# Amplifiers.net
KiCad netlist of a schematic drawn in Altium Designer
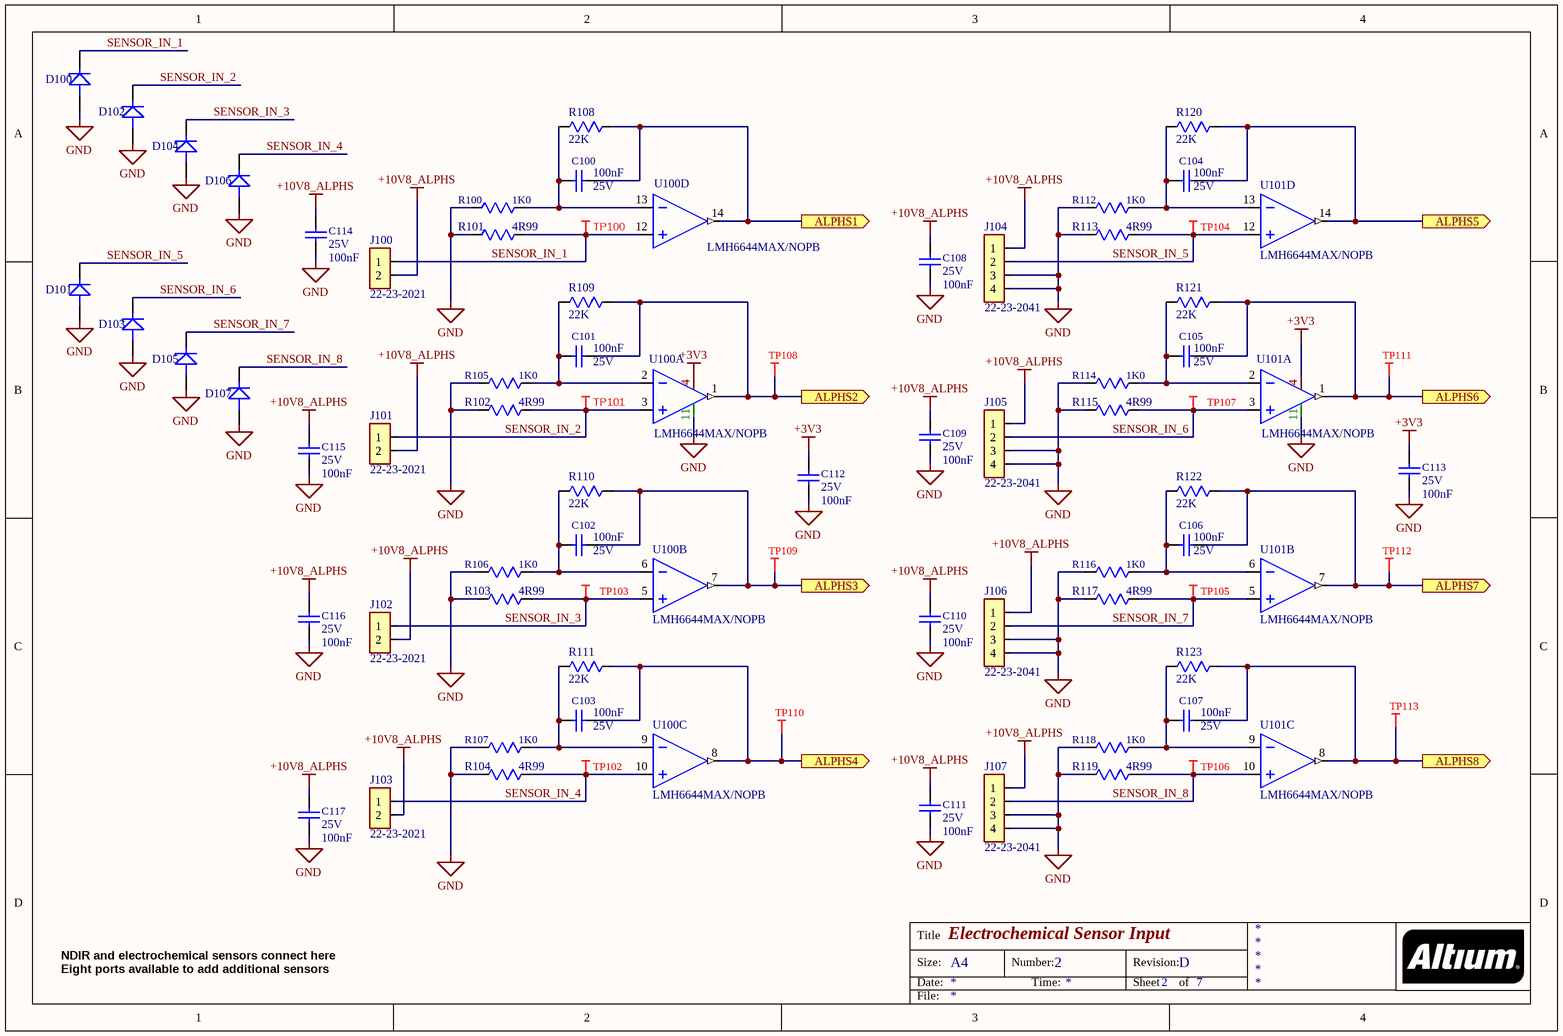
[diagram p0: Amplifiers.SchDoc]

(export (version "E")
  (design (tool "Eeschema 10.0.6"))
  (components
    (comp (ref "C100")
      (value "100nF")
      (footprint "CAPC1005X06N")
      (fields
        (field (name "VOLTAGE") "25V")
        (field (name "MANUFACTURER PART NUMBER") "CL05A104KA5NNNC")
        (field (name "MANUFACTURER") "Samsung")
        (field (name "Comment") "4.7uF")
      )
      (libsource (lib "Capacitors") (part "4.7uF_0603_10V"))
    )
    (comp (ref "C101")
      (value "100nF")
      (footprint "CAPC1005X06N")
      (fields
        (field (name "VOLTAGE") "25V")
        (field (name "MANUFACTURER PART NUMBER") "CL05A104KA5NNNC")
        (field (name "MANUFACTURER") "Samsung")
        (field (name "Comment") "4.7uF")
      )
      (libsource (lib "Capacitors") (part "4.7uF_0603_10V"))
    )
    (comp (ref "C102")
      (value "100nF")
      (footprint "CAPC1005X06N")
      (fields
        (field (name "VOLTAGE") "25V")
        (field (name "MANUFACTURER PART NUMBER") "CL05A104KA5NNNC")
        (field (name "MANUFACTURER") "Samsung")
        (field (name "Comment") "4.7uF")
      )
      (libsource (lib "Capacitors") (part "4.7uF_0603_10V"))
    )
    (comp (ref "C103")
      (value "100nF")
      (footprint "CAPC1005X06N")
      (fields
        (field (name "VOLTAGE") "25V")
        (field (name "MANUFACTURER PART NUMBER") "CL05A104KA5NNNC")
        (field (name "MANUFACTURER") "Samsung")
        (field (name "Comment") "4.7uF")
      )
      (libsource (lib "Capacitors") (part "4.7uF_0603_10V"))
    )
    (comp (ref "C104")
      (value "100nF")
      (footprint "CAPC1005X06N")
      (fields
        (field (name "VOLTAGE") "25V")
        (field (name "MANUFACTURER PART NUMBER") "CL05A104KA5NNNC")
        (field (name "MANUFACTURER") "Samsung")
        (field (name "Comment") "4.7uF")
      )
      (libsource (lib "Capacitors") (part "4.7uF_0603_10V"))
    )
    (comp (ref "C105")
      (value "100nF")
      (footprint "CAPC1005X06N")
      (fields
        (field (name "VOLTAGE") "25V")
        (field (name "MANUFACTURER PART NUMBER") "CL05A104KA5NNNC")
        (field (name "MANUFACTURER") "Samsung")
        (field (name "Comment") "4.7uF")
      )
      (libsource (lib "Capacitors") (part "4.7uF_0603_10V"))
    )
    (comp (ref "C106")
      (value "100nF")
      (footprint "CAPC1005X06N")
      (fields
        (field (name "VOLTAGE") "25V")
        (field (name "MANUFACTURER PART NUMBER") "CL05A104KA5NNNC")
        (field (name "MANUFACTURER") "Samsung")
        (field (name "Comment") "4.7uF")
      )
      (libsource (lib "Capacitors") (part "4.7uF_0603_10V"))
    )
    (comp (ref "C107")
      (value "100nF")
      (footprint "CAPC1005X06N")
      (fields
        (field (name "VOLTAGE") "25V")
        (field (name "MANUFACTURER PART NUMBER") "CL05A104KA5NNNC")
        (field (name "MANUFACTURER") "Samsung")
        (field (name "Comment") "4.7uF")
      )
      (libsource (lib "Capacitors") (part "4.7uF_0603_10V"))
    )
    (comp (ref "C108")
      (value "100nF")
      (footprint "CAPC1005X06N")
      (fields
        (field (name "VOLTAGE") "25V")
        (field (name "MANUFACTURER PART NUMBER") "CL05A104KA5NNNC")
        (field (name "MANUFACTURER") "Samsung")
        (field (name "Comment") "4.7uF")
      )
      (libsource (lib "Capacitors") (part "4.7uF_0603_10V"))
    )
    (comp (ref "C109")
      (value "100nF")
      (footprint "CAPC1005X06N")
      (fields
        (field (name "VOLTAGE") "25V")
        (field (name "MANUFACTURER PART NUMBER") "CL05A104KA5NNNC")
        (field (name "MANUFACTURER") "Samsung")
        (field (name "Comment") "4.7uF")
      )
      (libsource (lib "Capacitors") (part "4.7uF_0603_10V"))
    )
    (comp (ref "C110")
      (value "100nF")
      (footprint "CAPC1005X06N")
      (fields
        (field (name "VOLTAGE") "25V")
        (field (name "MANUFACTURER PART NUMBER") "CL05A104KA5NNNC")
        (field (name "MANUFACTURER") "Samsung")
        (field (name "Comment") "4.7uF")
      )
      (libsource (lib "Capacitors") (part "4.7uF_0603_10V"))
    )
    (comp (ref "C111")
      (value "100nF")
      (footprint "CAPC1005X06N")
      (fields
        (field (name "VOLTAGE") "25V")
        (field (name "MANUFACTURER PART NUMBER") "CL05A104KA5NNNC")
        (field (name "MANUFACTURER") "Samsung")
        (field (name "Comment") "4.7uF")
      )
      (libsource (lib "Capacitors") (part "4.7uF_0603_10V"))
    )
    (comp (ref "C112")
      (value "100nF")
      (footprint "CAPC1005X06N")
      (fields
        (field (name "VOLTAGE") "25V")
        (field (name "MANUFACTURER PART NUMBER") "CL05A104KA5NNNC")
        (field (name "MANUFACTURER") "Samsung")
        (field (name "Comment") "4.7uF")
      )
      (libsource (lib "Capacitors") (part "4.7uF_0603_10V"))
    )
    (comp (ref "C113")
      (value "100nF")
      (footprint "CAPC1005X06N")
      (fields
        (field (name "VOLTAGE") "25V")
        (field (name "MANUFACTURER PART NUMBER") "CL05A104KA5NNNC")
        (field (name "MANUFACTURER") "Samsung")
        (field (name "Comment") "4.7uF")
      )
      (libsource (lib "Capacitors") (part "4.7uF_0603_10V"))
    )
    (comp (ref "C114")
      (value "100nF")
      (footprint "CAPC1005X06N")
      (fields
        (field (name "VOLTAGE") "25V")
        (field (name "MANUFACTURER PART NUMBER") "CL05A104KA5NNNC")
        (field (name "MANUFACTURER") "Samsung")
        (field (name "Comment") "4.7uF")
      )
      (libsource (lib "Capacitors") (part "4.7uF_0603_10V"))
    )
    (comp (ref "C115")
      (value "100nF")
      (footprint "CAPC1005X06N")
      (fields
        (field (name "VOLTAGE") "25V")
        (field (name "MANUFACTURER PART NUMBER") "CL05A104KA5NNNC")
        (field (name "MANUFACTURER") "Samsung")
        (field (name "Comment") "4.7uF")
      )
      (libsource (lib "Capacitors") (part "4.7uF_0603_10V"))
    )
    (comp (ref "C116")
      (value "100nF")
      (footprint "CAPC1005X06N")
      (fields
        (field (name "VOLTAGE") "25V")
        (field (name "MANUFACTURER PART NUMBER") "CL05A104KA5NNNC")
        (field (name "MANUFACTURER") "Samsung")
        (field (name "Comment") "4.7uF")
      )
      (libsource (lib "Capacitors") (part "4.7uF_0603_10V"))
    )
    (comp (ref "C117")
      (value "100nF")
      (footprint "CAPC1005X06N")
      (fields
        (field (name "VOLTAGE") "25V")
        (field (name "MANUFACTURER PART NUMBER") "CL05A104KA5NNNC")
        (field (name "MANUFACTURER") "Samsung")
        (field (name "Comment") "4.7uF")
      )
      (libsource (lib "Capacitors") (part "4.7uF_0603_10V"))
    )
    (comp (ref "D100")
      (value "5V TVS")
      (footprint "NXP PTVSxS1UR-Series (SOD123W)")
      (fields
        (field (name "MANUFACTURER") "Nexperia")
        (field (name "MANUFACTURER PART NUMBER") "PTVS5V0S1UR,115")
      )
      (libsource (lib "FSM_2018") (part "NXP PTVSxS1UR-Series"))
    )
    (comp (ref "D101")
      (value "5V TVS")
      (footprint "NXP PTVSxS1UR-Series (SOD123W)")
      (fields
        (field (name "MANUFACTURER") "Nexperia")
        (field (name "MANUFACTURER PART NUMBER") "PTVS5V0S1UR,115")
      )
      (libsource (lib "FSM_2018") (part "NXP PTVSxS1UR-Series"))
    )
    (comp (ref "D102")
      (value "5V TVS")
      (footprint "NXP PTVSxS1UR-Series (SOD123W)")
      (fields
        (field (name "MANUFACTURER") "Nexperia")
        (field (name "MANUFACTURER PART NUMBER") "PTVS5V0S1UR,115")
      )
      (libsource (lib "FSM_2018") (part "NXP PTVSxS1UR-Series"))
    )
    (comp (ref "D103")
      (value "5V TVS")
      (footprint "NXP PTVSxS1UR-Series (SOD123W)")
      (fields
        (field (name "MANUFACTURER") "Nexperia")
        (field (name "MANUFACTURER PART NUMBER") "PTVS5V0S1UR,115")
      )
      (libsource (lib "FSM_2018") (part "NXP PTVSxS1UR-Series"))
    )
    (comp (ref "D104")
      (value "5V TVS")
      (footprint "NXP PTVSxS1UR-Series (SOD123W)")
      (fields
        (field (name "MANUFACTURER") "Nexperia")
        (field (name "MANUFACTURER PART NUMBER") "PTVS5V0S1UR,115")
      )
      (libsource (lib "FSM_2018") (part "NXP PTVSxS1UR-Series"))
    )
    (comp (ref "D105")
      (value "5V TVS")
      (footprint "NXP PTVSxS1UR-Series (SOD123W)")
      (fields
        (field (name "MANUFACTURER") "Nexperia")
        (field (name "MANUFACTURER PART NUMBER") "PTVS5V0S1UR,115")
      )
      (libsource (lib "FSM_2018") (part "NXP PTVSxS1UR-Series"))
    )
    (comp (ref "D106")
      (value "5V TVS")
      (footprint "NXP PTVSxS1UR-Series (SOD123W)")
      (fields
        (field (name "MANUFACTURER") "Nexperia")
        (field (name "MANUFACTURER PART NUMBER") "PTVS5V0S1UR,115")
      )
      (libsource (lib "FSM_2018") (part "NXP PTVSxS1UR-Series"))
    )
    (comp (ref "D107")
      (value "5V TVS")
      (footprint "NXP PTVSxS1UR-Series (SOD123W)")
      (fields
        (field (name "MANUFACTURER") "Nexperia")
        (field (name "MANUFACTURER PART NUMBER") "PTVS5V0S1UR,115")
      )
      (libsource (lib "FSM_2018") (part "NXP PTVSxS1UR-Series"))
    )
    (comp (ref "J100")
      (value "22-23-2021")
      (footprint "22-23-2021")
      (description "CONN HEADER VERT 2POS 2.54MM")
      (fields (field (name "MANUFACTURER") "Molex"))
      (libsource (lib "Gas Monitor Components") (part "22-23-2021"))
    )
    (comp (ref "J101")
      (value "22-23-2021")
      (footprint "22-23-2021")
      (description "CONN HEADER VERT 2POS 2.54MM")
      (fields (field (name "MANUFACTURER") "Molex"))
      (libsource (lib "Gas Monitor Components") (part "22-23-2021"))
    )
    (comp (ref "J102")
      (value "22-23-2021")
      (footprint "22-23-2021")
      (description "CONN HEADER VERT 2POS 2.54MM")
      (fields (field (name "MANUFACTURER") "Molex"))
      (libsource (lib "Gas Monitor Components") (part "22-23-2021"))
    )
    (comp (ref "J103")
      (value "22-23-2021")
      (footprint "22-23-2021")
      (description "CONN HEADER VERT 2POS 2.54MM")
      (fields (field (name "MANUFACTURER") "Molex"))
      (libsource (lib "Gas Monitor Components") (part "22-23-2021"))
    )
    (comp (ref "J104")
      (value "22-23-2041")
      (footprint "22-23-2041")
      (description "Connector Header Through Hole 4 position 0.100\" (2.54mm)")
      (fields (field (name "MANUFACTURER") "Molex") (field (name "MANUFACTURER PART NUMBER") "0022232041"))
      (libsource (lib "Gas Monitor Components") (part "22-23-2041"))
    )
    (comp (ref "J105")
      (value "22-23-2041")
      (footprint "22-23-2041")
      (description "Connector Header Through Hole 4 position 0.100\" (2.54mm)")
      (fields (field (name "MANUFACTURER") "Molex") (field (name "MANUFACTURER PART NUMBER") "0022232041"))
      (libsource (lib "Gas Monitor Components") (part "22-23-2041"))
    )
    (comp (ref "J106")
      (value "22-23-2041")
      (footprint "22-23-2041")
      (description "Connector Header Through Hole 4 position 0.100\" (2.54mm)")
      (fields (field (name "MANUFACTURER") "Molex") (field (name "MANUFACTURER PART NUMBER") "0022232041"))
      (libsource (lib "Gas Monitor Components") (part "22-23-2041"))
    )
    (comp (ref "J107")
      (value "22-23-2041")
      (footprint "22-23-2041")
      (description "Connector Header Through Hole 4 position 0.100\" (2.54mm)")
      (fields (field (name "MANUFACTURER") "Molex") (field (name "MANUFACTURER PART NUMBER") "0022232041"))
      (libsource (lib "Gas Monitor Components") (part "22-23-2041"))
    )
    (comp (ref "R100")
      (value "1K0")
      (footprint "RESC1005X03N")
      (description "RES 1K Ohm ±5%, 0.25W,1/4W 0603")
      (fields
        (field (name "MANUFACTURER") "Panasonic")
        (field (name "MANUFACTURER PART NUMBER") "ERJ-2RKF1001X")
      )
      (libsource (lib "Resistors") (part "1K00_0603_0.1W"))
    )
    (comp (ref "R101")
      (value "4R99")
      (footprint "RESC1005X03N")
      (description "Res,SMD,4R99,1/4W,5%")
      (fields
        (field (name "MANUFACTURER") "Stackpole")
        (field (name "MANUFACTURER PART NUMBER") "RMCF0402FT4R99")
      )
      (libsource (lib "Resistors") (part "4R99_0603_1/4W"))
    )
    (comp (ref "R102")
      (value "4R99")
      (footprint "RESC1005X03N")
      (description "Res,SMD,4R99,1/4W,5%")
      (fields
        (field (name "MANUFACTURER") "Stackpole")
        (field (name "MANUFACTURER PART NUMBER") "RMCF0402FT4R99")
      )
      (libsource (lib "Resistors") (part "4R99_0603_1/4W"))
    )
    (comp (ref "R103")
      (value "4R99")
      (footprint "RESC1005X03N")
      (description "Res,SMD,4R99,1/4W,5%")
      (fields
        (field (name "MANUFACTURER") "Stackpole")
        (field (name "MANUFACTURER PART NUMBER") "RMCF0402FT4R99")
      )
      (libsource (lib "Resistors") (part "4R99_0603_1/4W"))
    )
    (comp (ref "R104")
      (value "4R99")
      (footprint "RESC1005X03N")
      (description "Res,SMD,4R99,1/4W,5%")
      (fields
        (field (name "MANUFACTURER") "Stackpole")
        (field (name "MANUFACTURER PART NUMBER") "RMCF0402FT4R99")
      )
      (libsource (lib "Resistors") (part "4R99_0603_1/4W"))
    )
    (comp (ref "R105")
      (value "1K0")
      (footprint "RESC1005X03N")
      (description "RES 1K Ohm ±5%, 0.25W,1/4W 0603")
      (fields
        (field (name "MANUFACTURER") "Panasonic")
        (field (name "MANUFACTURER PART NUMBER") "ERJ-2RKF1001X")
      )
      (libsource (lib "Resistors") (part "1K00_0603_0.1W"))
    )
    (comp (ref "R106")
      (value "1K0")
      (footprint "RESC1005X03N")
      (description "RES 1K Ohm ±5%, 0.25W,1/4W 0603")
      (fields
        (field (name "MANUFACTURER") "Panasonic")
        (field (name "MANUFACTURER PART NUMBER") "ERJ-2RKF1001X")
      )
      (libsource (lib "Resistors") (part "1K00_0603_0.1W"))
    )
    (comp (ref "R107")
      (value "1K0")
      (footprint "RESC1005X03N")
      (description "RES 1K Ohm ±5%, 0.25W,1/4W 0603")
      (fields
        (field (name "MANUFACTURER") "Panasonic")
        (field (name "MANUFACTURER PART NUMBER") "ERJ-2RKF1001X")
      )
      (libsource (lib "Resistors") (part "1K00_0603_0.1W"))
    )
    (comp (ref "R108")
      (value "22K")
      (footprint "RESC1005X03N")
      (description "Res,SMD,22k,0603,5%,1/4W")
      (fields
        (field (name "MANUFACTURER PART NUMBER") "ERJ-2RKF2202X")
        (field (name "MANUFACTURER") "Panasonic")
      )
      (libsource (lib "Resistors") (part "22K_0603_1/4W"))
    )
    (comp (ref "R109")
      (value "22K")
      (footprint "RESC1005X03N")
      (description "Res,SMD,22k,0603,5%,1/4W")
      (fields
        (field (name "MANUFACTURER PART NUMBER") "ERJ-2RKF2202X")
        (field (name "MANUFACTURER") "Panasonic")
      )
      (libsource (lib "Resistors") (part "22K_0603_1/4W"))
    )
    (comp (ref "R110")
      (value "22K")
      (footprint "RESC1005X03N")
      (description "Res,SMD,22k,0603,5%,1/4W")
      (fields
        (field (name "MANUFACTURER PART NUMBER") "ERJ-2RKF2202X")
        (field (name "MANUFACTURER") "Panasonic")
      )
      (libsource (lib "Resistors") (part "22K_0603_1/4W"))
    )
    (comp (ref "R111")
      (value "22K")
      (footprint "RESC1005X03N")
      (description "Res,SMD,22k,0603,5%,1/4W")
      (fields
        (field (name "MANUFACTURER PART NUMBER") "ERJ-2RKF2202X")
        (field (name "MANUFACTURER") "Panasonic")
      )
      (libsource (lib "Resistors") (part "22K_0603_1/4W"))
    )
    (comp (ref "R112")
      (value "1K0")
      (footprint "RESC1005X03N")
      (description "RES 1K Ohm ±5%, 0.25W,1/4W 0603")
      (fields
        (field (name "MANUFACTURER") "Panasonic")
        (field (name "MANUFACTURER PART NUMBER") "ERJ-2RKF1001X")
      )
      (libsource (lib "Resistors") (part "1K00_0603_0.1W"))
    )
    (comp (ref "R113")
      (value "4R99")
      (footprint "RESC1005X03N")
      (description "Res,SMD,4R99,1/4W,5%")
      (fields
        (field (name "MANUFACTURER") "Stackpole")
        (field (name "MANUFACTURER PART NUMBER") "RMCF0402FT4R99")
      )
      (libsource (lib "Resistors") (part "4R99_0603_1/4W"))
    )
    (comp (ref "R114")
      (value "1K0")
      (footprint "RESC1005X03N")
      (description "RES 1K Ohm ±5%, 0.25W,1/4W 0603")
      (fields
        (field (name "MANUFACTURER") "Panasonic")
        (field (name "MANUFACTURER PART NUMBER") "ERJ-2RKF1001X")
      )
      (libsource (lib "Resistors") (part "1K00_0603_0.1W"))
    )
    (comp (ref "R115")
      (value "4R99")
      (footprint "RESC1005X03N")
      (description "Res,SMD,4R99,1/4W,5%")
      (fields
        (field (name "MANUFACTURER") "Stackpole")
        (field (name "MANUFACTURER PART NUMBER") "RMCF0402FT4R99")
      )
      (libsource (lib "Resistors") (part "4R99_0603_1/4W"))
    )
    (comp (ref "R116")
      (value "1K0")
      (footprint "RESC1005X03N")
      (description "RES 1K Ohm ±5%, 0.25W,1/4W 0603")
      (fields
        (field (name "MANUFACTURER") "Panasonic")
        (field (name "MANUFACTURER PART NUMBER") "ERJ-2RKF1001X")
      )
      (libsource (lib "Resistors") (part "1K00_0603_0.1W"))
    )
    (comp (ref "R117")
      (value "4R99")
      (footprint "RESC1005X03N")
      (description "Res,SMD,4R99,1/4W,5%")
      (fields
        (field (name "MANUFACTURER") "Stackpole")
        (field (name "MANUFACTURER PART NUMBER") "RMCF0402FT4R99")
      )
      (libsource (lib "Resistors") (part "4R99_0603_1/4W"))
    )
    (comp (ref "R118")
      (value "1K0")
      (footprint "RESC1005X03N")
      (description "RES 1K Ohm ±5%, 0.25W,1/4W 0603")
      (fields
        (field (name "MANUFACTURER") "Panasonic")
        (field (name "MANUFACTURER PART NUMBER") "ERJ-2RKF1001X")
      )
      (libsource (lib "Resistors") (part "1K00_0603_0.1W"))
    )
    (comp (ref "R119")
      (value "4R99")
      (footprint "RESC1005X03N")
      (description "Res,SMD,4R99,1/4W,5%")
      (fields
        (field (name "MANUFACTURER") "Stackpole")
        (field (name "MANUFACTURER PART NUMBER") "RMCF0402FT4R99")
      )
      (libsource (lib "Resistors") (part "4R99_0603_1/4W"))
    )
    (comp (ref "R120")
      (value "22K")
      (footprint "RESC1005X03N")
      (description "Res,SMD,22k,0603,5%,1/4W")
      (fields
        (field (name "MANUFACTURER PART NUMBER") "ERJ-2RKF2202X")
        (field (name "MANUFACTURER") "Panasonic")
      )
      (libsource (lib "Resistors") (part "22K_0603_1/4W"))
    )
    (comp (ref "R121")
      (value "22K")
      (footprint "RESC1005X03N")
      (description "Res,SMD,22k,0603,5%,1/4W")
      (fields
        (field (name "MANUFACTURER PART NUMBER") "ERJ-2RKF2202X")
        (field (name "MANUFACTURER") "Panasonic")
      )
      (libsource (lib "Resistors") (part "22K_0603_1/4W"))
    )
    (comp (ref "R122")
      (value "22K")
      (footprint "RESC1005X03N")
      (description "Res,SMD,22k,0603,5%,1/4W")
      (fields
        (field (name "MANUFACTURER PART NUMBER") "ERJ-2RKF2202X")
        (field (name "MANUFACTURER") "Panasonic")
      )
      (libsource (lib "Resistors") (part "22K_0603_1/4W"))
    )
    (comp (ref "R123")
      (value "22K")
      (footprint "RESC1005X03N")
      (description "Res,SMD,22k,0603,5%,1/4W")
      (fields
        (field (name "MANUFACTURER PART NUMBER") "ERJ-2RKF2202X")
        (field (name "MANUFACTURER") "Panasonic")
      )
      (libsource (lib "Resistors") (part "22K_0603_1/4W"))
    )
    (comp (ref "TP100")
      (value "PAD")
      (footprint "TP_SMD_39MIL")
      (description "SMD Test Pad")
      (fields (field (name "MANUFACTURER") "No P/N Required"))
      (libsource (lib "Connectors") (part "TP_SMD_39MIL"))
    )
    (comp (ref "TP101")
      (value "PAD")
      (footprint "TP_SMD_39MIL")
      (description "SMD Test Pad")
      (fields (field (name "MANUFACTURER") "No P/N Required"))
      (libsource (lib "Connectors") (part "TP_SMD_39MIL"))
    )
    (comp (ref "TP102")
      (value "PAD")
      (footprint "TP_SMD_39MIL")
      (description "SMD Test Pad")
      (fields (field (name "MANUFACTURER") "No P/N Required"))
      (libsource (lib "Connectors") (part "TP_SMD_39MIL"))
    )
    (comp (ref "TP103")
      (value "PAD")
      (footprint "TP_SMD_39MIL")
      (description "SMD Test Pad")
      (fields (field (name "MANUFACTURER") "No P/N Required"))
      (libsource (lib "Connectors") (part "TP_SMD_39MIL"))
    )
    (comp (ref "TP104")
      (value "PAD")
      (footprint "TP_SMD_39MIL")
      (description "SMD Test Pad")
      (fields (field (name "MANUFACTURER") "No P/N Required"))
      (libsource (lib "Connectors") (part "TP_SMD_39MIL"))
    )
    (comp (ref "TP105")
      (value "PAD")
      (footprint "TP_SMD_39MIL")
      (description "SMD Test Pad")
      (fields (field (name "MANUFACTURER") "No P/N Required"))
      (libsource (lib "Connectors") (part "TP_SMD_39MIL"))
    )
    (comp (ref "TP106")
      (value "PAD")
      (footprint "TP_SMD_39MIL")
      (description "SMD Test Pad")
      (fields (field (name "MANUFACTURER") "No P/N Required"))
      (libsource (lib "Connectors") (part "TP_SMD_39MIL"))
    )
    (comp (ref "TP107")
      (value "PAD")
      (footprint "TP_SMD_39MIL")
      (description "SMD Test Pad")
      (fields (field (name "MANUFACTURER") "No P/N Required"))
      (libsource (lib "Connectors") (part "TP_SMD_39MIL"))
    )
    (comp (ref "TP108")
      (value "PAD")
      (footprint "TP_SMD_39MIL")
      (description "SMD Test Pad")
      (fields (field (name "MANUFACTURER") "No P/N Required"))
      (libsource (lib "Connectors") (part "TP_SMD_39MIL"))
    )
    (comp (ref "TP109")
      (value "PAD")
      (footprint "TP_SMD_39MIL")
      (description "SMD Test Pad")
      (fields (field (name "MANUFACTURER") "No P/N Required"))
      (libsource (lib "Connectors") (part "TP_SMD_39MIL"))
    )
    (comp (ref "TP110")
      (value "PAD")
      (footprint "TP_SMD_39MIL")
      (description "SMD Test Pad")
      (fields (field (name "MANUFACTURER") "No P/N Required"))
      (libsource (lib "Connectors") (part "TP_SMD_39MIL"))
    )
    (comp (ref "TP111")
      (value "PAD")
      (footprint "TP_SMD_39MIL")
      (description "SMD Test Pad")
      (fields (field (name "MANUFACTURER") "No P/N Required"))
      (libsource (lib "Connectors") (part "TP_SMD_39MIL"))
    )
    (comp (ref "TP112")
      (value "PAD")
      (footprint "TP_SMD_39MIL")
      (description "SMD Test Pad")
      (fields (field (name "MANUFACTURER") "No P/N Required"))
      (libsource (lib "Connectors") (part "TP_SMD_39MIL"))
    )
    (comp (ref "TP113")
      (value "PAD")
      (footprint "TP_SMD_39MIL")
      (description "SMD Test Pad")
      (fields (field (name "MANUFACTURER") "No P/N Required"))
      (libsource (lib "Connectors") (part "TP_SMD_39MIL"))
    )
    (comp (ref "U100")
      (value "LMH6644MAX/NOPB")
      (footprint "SOIC-14")
      (description "Quad opamplifiers")
      (fields (field (name "MANUFACTURER") "Texas Instruments"))
      (libsource (lib "VolcDB") (part "LM660"))
    )
    (comp (ref "U101")
      (value "LMH6644MAX/NOPB")
      (footprint "SOIC-14")
      (description "Quad opamplifiers")
      (fields (field (name "MANUFACTURER") "Texas Instruments"))
      (libsource (lib "VolcDB") (part "LM660"))
    )
  )
  (nets
    (net (code "1") (name "+3V3") (class "Default")
      (node (ref "C112") (pin "2") (pintype "passive"))
      (node (ref "C113") (pin "2") (pintype "passive"))
      (node (ref "U100") (pin "4") (pinfunction "Vdd_4") (pintype "passive"))
      (node (ref "U101") (pin "4") (pinfunction "Vdd_4") (pintype "passive"))
    )
    (net (code "2") (name "+10V8_ALPHS") (class "Default")
      (node (ref "C108") (pin "2") (pintype "passive"))
      (node (ref "C109") (pin "2") (pintype "passive"))
      (node (ref "C110") (pin "2") (pintype "passive"))
      (node (ref "C111") (pin "2") (pintype "passive"))
      (node (ref "C114") (pin "2") (pintype "passive"))
      (node (ref "C115") (pin "2") (pintype "passive"))
      (node (ref "C116") (pin "2") (pintype "passive"))
      (node (ref "C117") (pin "2") (pintype "passive"))
      (node (ref "J100") (pin "2") (pinfunction "2_2") (pintype "passive"))
      (node (ref "J101") (pin "2") (pinfunction "2_2") (pintype "passive"))
      (node (ref "J102") (pin "2") (pinfunction "2_2") (pintype "passive"))
      (node (ref "J103") (pin "2") (pinfunction "2_2") (pintype "passive"))
      (node (ref "J104") (pin "1") (pinfunction "1_1") (pintype "passive"))
      (node (ref "J105") (pin "1") (pinfunction "1_1") (pintype "passive"))
      (node (ref "J106") (pin "1") (pinfunction "1_1") (pintype "passive"))
      (node (ref "J107") (pin "1") (pinfunction "1_1") (pintype "passive"))
    )
    (net (code "3") (name "/ALPHS1") (class "Default")
      (node (ref "C100") (pin "2") (pintype "passive"))
      (node (ref "R108") (pin "2") (pintype "passive"))
      (node (ref "U100") (pin "14") (pinfunction "OutD_14") (pintype "output"))
    )
    (net (code "4") (name "/ALPHS2") (class "Default")
      (node (ref "C101") (pin "2") (pintype "passive"))
      (node (ref "R109") (pin "2") (pintype "passive"))
      (node (ref "TP108") (pin "1") (pintype "passive"))
      (node (ref "U100") (pin "1") (pinfunction "OutA_1") (pintype "output"))
    )
    (net (code "5") (name "/ALPHS3") (class "Default")
      (node (ref "C102") (pin "2") (pintype "passive"))
      (node (ref "R110") (pin "2") (pintype "passive"))
      (node (ref "TP109") (pin "1") (pintype "passive"))
      (node (ref "U100") (pin "7") (pinfunction "OutB_7") (pintype "output"))
    )
    (net (code "6") (name "/ALPHS4") (class "Default")
      (node (ref "C103") (pin "2") (pintype "passive"))
      (node (ref "R111") (pin "2") (pintype "passive"))
      (node (ref "TP110") (pin "1") (pintype "passive"))
      (node (ref "U100") (pin "8") (pinfunction "OutC_8") (pintype "output"))
    )
    (net (code "7") (name "/ALPHS5") (class "Default")
      (node (ref "C104") (pin "2") (pintype "passive"))
      (node (ref "R120") (pin "2") (pintype "passive"))
      (node (ref "U101") (pin "14") (pinfunction "OutD_14") (pintype "output"))
    )
    (net (code "8") (name "/ALPHS6") (class "Default")
      (node (ref "C105") (pin "2") (pintype "passive"))
      (node (ref "R121") (pin "2") (pintype "passive"))
      (node (ref "TP111") (pin "1") (pintype "passive"))
      (node (ref "U101") (pin "1") (pinfunction "OutA_1") (pintype "output"))
    )
    (net (code "9") (name "/ALPHS7") (class "Default")
      (node (ref "C106") (pin "2") (pintype "passive"))
      (node (ref "R122") (pin "2") (pintype "passive"))
      (node (ref "TP112") (pin "1") (pintype "passive"))
      (node (ref "U101") (pin "7") (pinfunction "OutB_7") (pintype "output"))
    )
    (net (code "10") (name "/ALPHS8") (class "Default")
      (node (ref "C107") (pin "2") (pintype "passive"))
      (node (ref "R123") (pin "2") (pintype "passive"))
      (node (ref "TP113") (pin "1") (pintype "passive"))
      (node (ref "U101") (pin "8") (pinfunction "OutC_8") (pintype "output"))
    )
    (net (code "11") (name "/SENSOR_IN_1") (class "Default")
      (node (ref "D100") (pin "1") (pinfunction "1_1") (pintype "passive"))
      (node (ref "J100") (pin "1") (pinfunction "1_1") (pintype "passive"))
      (node (ref "R101") (pin "2") (pintype "passive"))
      (node (ref "TP100") (pin "1") (pintype "passive"))
      (node (ref "U100") (pin "12") (pinfunction "+InD_12") (pintype "passive"))
    )
    (net (code "12") (name "/SENSOR_IN_2") (class "Default")
      (node (ref "D102") (pin "1") (pinfunction "1_1") (pintype "passive"))
      (node (ref "J101") (pin "1") (pinfunction "1_1") (pintype "passive"))
      (node (ref "R102") (pin "2") (pintype "passive"))
      (node (ref "TP101") (pin "1") (pintype "passive"))
      (node (ref "U100") (pin "3") (pinfunction "+InA_3") (pintype "passive"))
    )
    (net (code "13") (name "/SENSOR_IN_3") (class "Default")
      (node (ref "D104") (pin "1") (pinfunction "1_1") (pintype "passive"))
      (node (ref "J102") (pin "1") (pinfunction "1_1") (pintype "passive"))
      (node (ref "R103") (pin "2") (pintype "passive"))
      (node (ref "TP103") (pin "1") (pintype "passive"))
      (node (ref "U100") (pin "5") (pinfunction "+InB_5") (pintype "passive"))
    )
    (net (code "14") (name "/SENSOR_IN_4") (class "Default")
      (node (ref "D106") (pin "1") (pinfunction "1_1") (pintype "passive"))
      (node (ref "J103") (pin "1") (pinfunction "1_1") (pintype "passive"))
      (node (ref "R104") (pin "2") (pintype "passive"))
      (node (ref "TP102") (pin "1") (pintype "passive"))
      (node (ref "U100") (pin "10") (pinfunction "+InC_10") (pintype "passive"))
    )
    (net (code "15") (name "/SENSOR_IN_5") (class "Default")
      (node (ref "D101") (pin "1") (pinfunction "1_1") (pintype "passive"))
      (node (ref "J104") (pin "2") (pinfunction "2_2") (pintype "passive"))
      (node (ref "R113") (pin "2") (pintype "passive"))
      (node (ref "TP104") (pin "1") (pintype "passive"))
      (node (ref "U101") (pin "12") (pinfunction "+InD_12") (pintype "passive"))
    )
    (net (code "16") (name "/SENSOR_IN_6") (class "Default")
      (node (ref "D103") (pin "1") (pinfunction "1_1") (pintype "passive"))
      (node (ref "J105") (pin "2") (pinfunction "2_2") (pintype "passive"))
      (node (ref "R115") (pin "2") (pintype "passive"))
      (node (ref "TP107") (pin "1") (pintype "passive"))
      (node (ref "U101") (pin "3") (pinfunction "+InA_3") (pintype "passive"))
    )
    (net (code "17") (name "/SENSOR_IN_7") (class "Default")
      (node (ref "D105") (pin "1") (pinfunction "1_1") (pintype "passive"))
      (node (ref "J106") (pin "2") (pinfunction "2_2") (pintype "passive"))
      (node (ref "R117") (pin "2") (pintype "passive"))
      (node (ref "TP105") (pin "1") (pintype "passive"))
      (node (ref "U101") (pin "5") (pinfunction "+InB_5") (pintype "passive"))
    )
    (net (code "18") (name "/SENSOR_IN_8") (class "Default")
      (node (ref "D107") (pin "1") (pinfunction "1_1") (pintype "passive"))
      (node (ref "J107") (pin "2") (pinfunction "2_2") (pintype "passive"))
      (node (ref "R119") (pin "2") (pintype "passive"))
      (node (ref "TP106") (pin "1") (pintype "passive"))
      (node (ref "U101") (pin "10") (pinfunction "+InC_10") (pintype "passive"))
    )
    (net (code "19") (name "GND") (class "Default")
      (node (ref "C108") (pin "1") (pintype "passive"))
      (node (ref "C109") (pin "1") (pintype "passive"))
      (node (ref "C110") (pin "1") (pintype "passive"))
      (node (ref "C111") (pin "1") (pintype "passive"))
      (node (ref "C112") (pin "1") (pintype "passive"))
      (node (ref "C113") (pin "1") (pintype "passive"))
      (node (ref "C114") (pin "1") (pintype "passive"))
      (node (ref "C115") (pin "1") (pintype "passive"))
      (node (ref "C116") (pin "1") (pintype "passive"))
      (node (ref "C117") (pin "1") (pintype "passive"))
      (node (ref "D100") (pin "2") (pinfunction "2_2") (pintype "passive"))
      (node (ref "D101") (pin "2") (pinfunction "2_2") (pintype "passive"))
      (node (ref "D102") (pin "2") (pinfunction "2_2") (pintype "passive"))
      (node (ref "D103") (pin "2") (pinfunction "2_2") (pintype "passive"))
      (node (ref "D104") (pin "2") (pinfunction "2_2") (pintype "passive"))
      (node (ref "D105") (pin "2") (pinfunction "2_2") (pintype "passive"))
      (node (ref "D106") (pin "2") (pinfunction "2_2") (pintype "passive"))
      (node (ref "D107") (pin "2") (pinfunction "2_2") (pintype "passive"))
      (node (ref "J104") (pin "3") (pinfunction "3_3") (pintype "passive"))
      (node (ref "J104") (pin "4") (pinfunction "4_4") (pintype "passive"))
      (node (ref "J105") (pin "3") (pinfunction "3_3") (pintype "passive"))
      (node (ref "J105") (pin "4") (pinfunction "4_4") (pintype "passive"))
      (node (ref "J106") (pin "3") (pinfunction "3_3") (pintype "passive"))
      (node (ref "J106") (pin "4") (pinfunction "4_4") (pintype "passive"))
      (node (ref "J107") (pin "3") (pinfunction "3_3") (pintype "passive"))
      (node (ref "J107") (pin "4") (pinfunction "4_4") (pintype "passive"))
      (node (ref "R100") (pin "1") (pintype "passive"))
      (node (ref "R101") (pin "1") (pintype "passive"))
      (node (ref "R102") (pin "1") (pintype "passive"))
      (node (ref "R103") (pin "1") (pintype "passive"))
      (node (ref "R104") (pin "1") (pintype "passive"))
      (node (ref "R105") (pin "1") (pintype "passive"))
      (node (ref "R106") (pin "1") (pintype "passive"))
      (node (ref "R107") (pin "1") (pintype "passive"))
      (node (ref "R112") (pin "1") (pintype "passive"))
      (node (ref "R113") (pin "1") (pintype "passive"))
      (node (ref "R114") (pin "1") (pintype "passive"))
      (node (ref "R115") (pin "1") (pintype "passive"))
      (node (ref "R116") (pin "1") (pintype "passive"))
      (node (ref "R117") (pin "1") (pintype "passive"))
      (node (ref "R118") (pin "1") (pintype "passive"))
      (node (ref "R119") (pin "1") (pintype "passive"))
      (node (ref "U100") (pin "11") (pinfunction "Vss_11") (pintype "passive"))
      (node (ref "U101") (pin "11") (pinfunction "Vss_11") (pintype "passive"))
    )
    (net (code "20") (name "Net-(U100A--InA)") (class "Default")
      (node (ref "C101") (pin "1") (pintype "passive"))
      (node (ref "R105") (pin "2") (pintype "passive"))
      (node (ref "R109") (pin "1") (pintype "passive"))
      (node (ref "U100") (pin "2") (pinfunction "-InA_2") (pintype "passive"))
    )
    (net (code "21") (name "Net-(U100B--InB)") (class "Default")
      (node (ref "C102") (pin "1") (pintype "passive"))
      (node (ref "R106") (pin "2") (pintype "passive"))
      (node (ref "R110") (pin "1") (pintype "passive"))
      (node (ref "U100") (pin "6") (pinfunction "-InB_6") (pintype "passive"))
    )
    (net (code "22") (name "Net-(U100C--InC)") (class "Default")
      (node (ref "C103") (pin "1") (pintype "passive"))
      (node (ref "R107") (pin "2") (pintype "passive"))
      (node (ref "R111") (pin "1") (pintype "passive"))
      (node (ref "U100") (pin "9") (pinfunction "-InC_9") (pintype "passive"))
    )
    (net (code "23") (name "Net-(U100D--InD)") (class "Default")
      (node (ref "C100") (pin "1") (pintype "passive"))
      (node (ref "R100") (pin "2") (pintype "passive"))
      (node (ref "R108") (pin "1") (pintype "passive"))
      (node (ref "U100") (pin "13") (pinfunction "-InD_13") (pintype "passive"))
    )
    (net (code "24") (name "Net-(U101A--InA)") (class "Default")
      (node (ref "C105") (pin "1") (pintype "passive"))
      (node (ref "R114") (pin "2") (pintype "passive"))
      (node (ref "R121") (pin "1") (pintype "passive"))
      (node (ref "U101") (pin "2") (pinfunction "-InA_2") (pintype "passive"))
    )
    (net (code "25") (name "Net-(U101B--InB)") (class "Default")
      (node (ref "C106") (pin "1") (pintype "passive"))
      (node (ref "R116") (pin "2") (pintype "passive"))
      (node (ref "R122") (pin "1") (pintype "passive"))
      (node (ref "U101") (pin "6") (pinfunction "-InB_6") (pintype "passive"))
    )
    (net (code "26") (name "Net-(U101C--InC)") (class "Default")
      (node (ref "C107") (pin "1") (pintype "passive"))
      (node (ref "R118") (pin "2") (pintype "passive"))
      (node (ref "R123") (pin "1") (pintype "passive"))
      (node (ref "U101") (pin "9") (pinfunction "-InC_9") (pintype "passive"))
    )
    (net (code "27") (name "Net-(U101D--InD)") (class "Default")
      (node (ref "C104") (pin "1") (pintype "passive"))
      (node (ref "R112") (pin "2") (pintype "passive"))
      (node (ref "R120") (pin "1") (pintype "passive"))
      (node (ref "U101") (pin "13") (pinfunction "-InD_13") (pintype "passive"))
    )
  )
)
